# Kajtu_-DSP_analog_out.net
KiCad netlist of a schematic drawn in Altium Designer
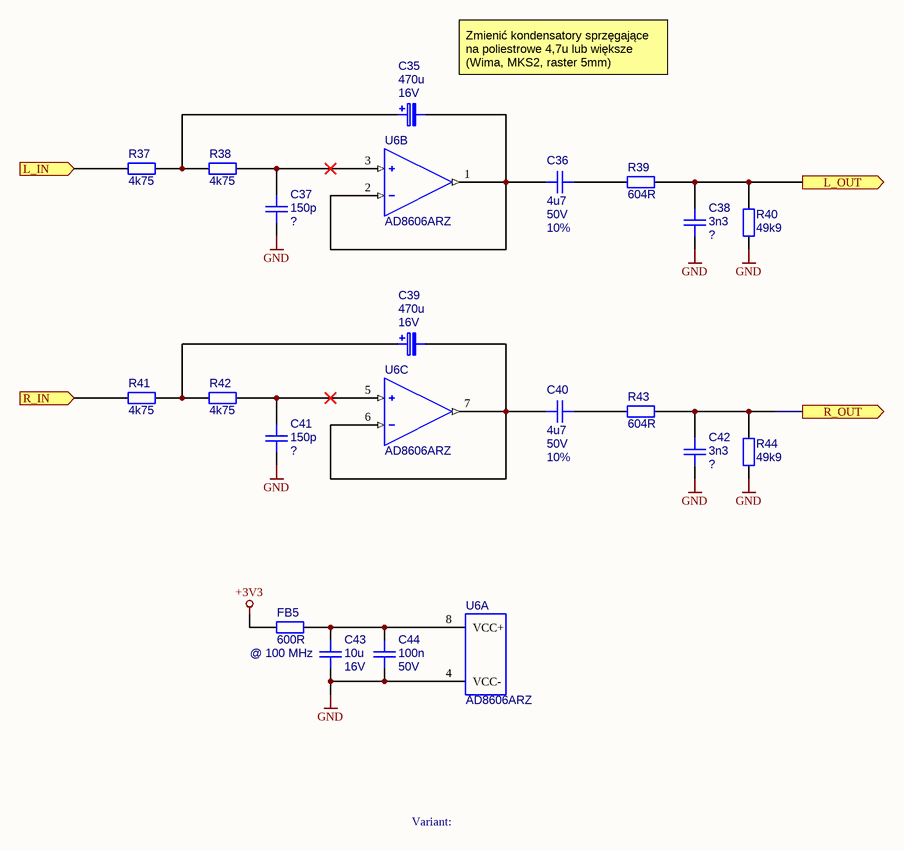
[diagram p0: Kajtuś-DSP_analog_out.SchDoc]

(export (version "E")
  (design (tool "Eeschema 10.0.6"))
  (components
    (comp (ref "C35")
      (value "470u")
      (footprint "CE_R3.5-D8-H11.5")
      (description "Kondensator elektrolityczny THD")
      (fields
        (field (name "PART NUMBER") "CE_R3.5-D8-H11.5_470u_16V")
        (field (name "MANUFACTURER") "Nichicon")
        (field (name "VOLTAGE") "16V")
      )
      (libsource (lib "AD_ostry_intlib") (part "CE_R3.5-D8-H11.5_470u_16V"))
    )
    (comp (ref "C36")
      (value "4u7")
      (footprint "C_R5-L7.2-W7.2-H13")
      (description "Kondensator tworzywowy")
      (fields
        (field (name "PART NUMBER") "C_R5-L7.2-W7.2-H13_4u7_50V_MKS2_10%")
        (field (name "MANUFACTURER") "Wima")
        (field (name "VOLTAGE") "50V")
        (field (name "TOLERANCE") "10%")
      )
      (libsource (lib "AD_ostry_intlib") (part "C_R5-L7.2-W7.2-H13_4u7_50V_MKS2_10%"))
    )
    (comp (ref "C37")
      (value "150p")
      (footprint "C_0603_MA")
      (description "Kondensator ceramiczny SMD")
      (fields (field (name "PART NUMBER") "C_SMD_MLCC_generic") (field (name "VOLTAGE") "?"))
      (libsource (lib "AD_ostry_intlib") (part "C_SMD_MLCC_generic"))
    )
    (comp (ref "C38")
      (value "3n3")
      (footprint "C_0603_MA")
      (description "Kondensator ceramiczny SMD")
      (fields (field (name "PART NUMBER") "C_SMD_MLCC_generic") (field (name "VOLTAGE") "?"))
      (libsource (lib "AD_ostry_intlib") (part "C_SMD_MLCC_generic"))
    )
    (comp (ref "C39")
      (value "470u")
      (footprint "CE_R3.5-D8-H11.5")
      (description "Kondensator elektrolityczny THD")
      (fields
        (field (name "PART NUMBER") "CE_R3.5-D8-H11.5_470u_16V")
        (field (name "MANUFACTURER") "Nichicon")
        (field (name "VOLTAGE") "16V")
      )
      (libsource (lib "AD_ostry_intlib") (part "CE_R3.5-D8-H11.5_470u_16V"))
    )
    (comp (ref "C40")
      (value "4u7")
      (footprint "C_R5-L7.2-W7.2-H13")
      (description "Kondensator tworzywowy")
      (fields
        (field (name "PART NUMBER") "C_R5-L7.2-W7.2-H13_4u7_50V_MKS2_10%")
        (field (name "MANUFACTURER") "Wima")
        (field (name "VOLTAGE") "50V")
        (field (name "TOLERANCE") "10%")
      )
      (libsource (lib "AD_ostry_intlib") (part "C_R5-L7.2-W7.2-H13_4u7_50V_MKS2_10%"))
    )
    (comp (ref "C41")
      (value "150p")
      (footprint "C_0603_MA")
      (description "Kondensator ceramiczny SMD")
      (fields (field (name "PART NUMBER") "C_SMD_MLCC_generic") (field (name "VOLTAGE") "?"))
      (libsource (lib "AD_ostry_intlib") (part "C_SMD_MLCC_generic"))
    )
    (comp (ref "C42")
      (value "3n3")
      (footprint "C_0603_MA")
      (description "Kondensator ceramiczny SMD")
      (fields (field (name "PART NUMBER") "C_SMD_MLCC_generic") (field (name "VOLTAGE") "?"))
      (libsource (lib "AD_ostry_intlib") (part "C_SMD_MLCC_generic"))
    )
    (comp (ref "C43")
      (value "10u")
      (footprint "C_0805_MA")
      (description "Kondensator ceramiczny SMD")
      (fields (field (name "PART NUMBER") "C_0805_10u_16V_X5R") (field (name "VOLTAGE") "16V"))
      (libsource (lib "AD_ostry_intlib") (part "C_0805_10u_16V_X5R"))
    )
    (comp (ref "C44")
      (value "100n")
      (footprint "C_0603_MA")
      (description "Kondensator ceramiczny SMD")
      (fields (field (name "PART NUMBER") "C_0603_100n_50V_X7R") (field (name "VOLTAGE") "50V"))
      (libsource (lib "AD_ostry_intlib") (part "C_0603_100n_50V_X7R"))
    )
    (comp (ref "FB5")
      (value "600R")
      (footprint "R_0603_MA")
      (description "Koralik ferrytowy")
      (fields
        (field (name "MANUFACTURER") "Yageo")
        (field (name "PART NUMBER") "FB_0603_PBY160808T-601Y_600R_1A")
        (field (name "@ FREQUENCY") "@ 100 MHz")
      )
      (libsource (lib "AD_ostry_intlib") (part "FB_0603_PBY160808T-601Y_600R_1A"))
    )
    (comp (ref "R37")
      (value "4k75")
      (footprint "R_1206_MA")
      (description "SMD resistor")
      (fields (field (name "PART NUMBER") "?"))
      (libsource (lib "AD_ostry_intlib") (part "R_SMD_generic"))
    )
    (comp (ref "R38")
      (value "4k75")
      (footprint "R_1206_MA")
      (description "SMD resistor")
      (fields (field (name "PART NUMBER") "?"))
      (libsource (lib "AD_ostry_intlib") (part "R_SMD_generic"))
    )
    (comp (ref "R39")
      (value "604R")
      (footprint "R_1206_MA")
      (description "SMD resistor")
      (fields (field (name "PART NUMBER") "?"))
      (libsource (lib "AD_ostry_intlib") (part "R_SMD_generic"))
    )
    (comp (ref "R40")
      (value "49k9")
      (footprint "R_1206_MA")
      (description "SMD resistor")
      (fields (field (name "PART NUMBER") "?"))
      (libsource (lib "AD_ostry_intlib") (part "R_SMD_generic"))
    )
    (comp (ref "R41")
      (value "4k75")
      (footprint "R_1206_MA")
      (description "SMD resistor")
      (fields (field (name "PART NUMBER") "?"))
      (libsource (lib "AD_ostry_intlib") (part "R_SMD_generic"))
    )
    (comp (ref "R42")
      (value "4k75")
      (footprint "R_1206_MA")
      (description "SMD resistor")
      (fields (field (name "PART NUMBER") "?"))
      (libsource (lib "AD_ostry_intlib") (part "R_SMD_generic"))
    )
    (comp (ref "R43")
      (value "604R")
      (footprint "R_1206_MA")
      (description "SMD resistor")
      (fields (field (name "PART NUMBER") "?"))
      (libsource (lib "AD_ostry_intlib") (part "R_SMD_generic"))
    )
    (comp (ref "R44")
      (value "49k9")
      (footprint "R_1206_MA")
      (description "SMD resistor")
      (fields (field (name "PART NUMBER") "?"))
      (libsource (lib "AD_ostry_intlib") (part "R_SMD_generic"))
    )
    (comp (ref "U6")
      (value "AD8606ARZ")
      (footprint "SO-8")
      (description "Precision, Low Noise, CMOS, Rail-to-Rail, Input/Output Operational Amplifier")
      (fields (field (name "MANUFACTURER") "Analog Devices"))
      (libsource (lib "") (part "U_AD8606ARZ_1"))
    )
  )
  (nets
    (net (code "1") (name "+3V3") (class "Default")
      (node (ref "FB5") (pin "1") (pinfunction "1_1") (pintype "passive"))
    )
    (net (code "2") (name "/L_IN") (class "Default")
      (node (ref "R37") (pin "2") (pinfunction "2_2") (pintype "passive"))
    )
    (net (code "3") (name "/L_OUT") (class "Default")
      (node (ref "C38") (pin "1") (pinfunction "1_1") (pintype "passive"))
      (node (ref "R39") (pin "1") (pinfunction "1_1") (pintype "passive"))
      (node (ref "R40") (pin "1") (pinfunction "1_1") (pintype "passive"))
    )
    (net (code "4") (name "/R_IN") (class "Default")
      (node (ref "R41") (pin "2") (pinfunction "2_2") (pintype "passive"))
    )
    (net (code "5") (name "/R_OUT") (class "Default")
      (node (ref "C42") (pin "1") (pinfunction "1_1") (pintype "passive"))
      (node (ref "R43") (pin "1") (pinfunction "1_1") (pintype "passive"))
      (node (ref "R44") (pin "1") (pinfunction "1_1") (pintype "passive"))
    )
    (net (code "6") (name "GND") (class "Default")
      (node (ref "C37") (pin "2") (pinfunction "2_2") (pintype "passive"))
      (node (ref "C38") (pin "2") (pinfunction "2_2") (pintype "passive"))
      (node (ref "C41") (pin "2") (pinfunction "2_2") (pintype "passive"))
      (node (ref "C42") (pin "2") (pinfunction "2_2") (pintype "passive"))
      (node (ref "C43") (pin "2") (pinfunction "2_2") (pintype "passive"))
      (node (ref "C44") (pin "2") (pinfunction "2_2") (pintype "passive"))
      (node (ref "R40") (pin "2") (pinfunction "2_2") (pintype "passive"))
      (node (ref "R44") (pin "2") (pinfunction "2_2") (pintype "passive"))
      (node (ref "U6") (pin "4") (pinfunction "VCC-_4") (pintype "power_in"))
    )
    (net (code "7") (name "Net-(C35-Pad1)") (class "Default")
      (node (ref "C35") (pin "1") (pinfunction "1_1") (pintype "passive"))
      (node (ref "R37") (pin "1") (pinfunction "1_1") (pintype "passive"))
      (node (ref "R38") (pin "2") (pinfunction "2_2") (pintype "passive"))
    )
    (net (code "8") (name "Net-(C36-Pad2)") (class "Default")
      (node (ref "C36") (pin "2") (pinfunction "2_2") (pintype "passive"))
      (node (ref "R39") (pin "2") (pinfunction "2_2") (pintype "passive"))
    )
    (net (code "9") (name "Net-(C39-Pad1)") (class "Default")
      (node (ref "C39") (pin "1") (pinfunction "1_1") (pintype "passive"))
      (node (ref "R41") (pin "1") (pinfunction "1_1") (pintype "passive"))
      (node (ref "R42") (pin "2") (pinfunction "2_2") (pintype "passive"))
    )
    (net (code "10") (name "Net-(C40-Pad2)") (class "Default")
      (node (ref "C40") (pin "2") (pinfunction "2_2") (pintype "passive"))
      (node (ref "R43") (pin "2") (pinfunction "2_2") (pintype "passive"))
    )
    (net (code "11") (name "Net-(U6A-VCC+)") (class "Default")
      (node (ref "C43") (pin "1") (pinfunction "1_1") (pintype "passive"))
      (node (ref "C44") (pin "1") (pinfunction "1_1") (pintype "passive"))
      (node (ref "FB5") (pin "2") (pinfunction "2_2") (pintype "passive"))
      (node (ref "U6") (pin "8") (pinfunction "VCC+_8") (pintype "power_in"))
    )
    (net (code "12") (name "Net-(U6B-+IN)") (class "Default")
      (node (ref "C37") (pin "1") (pinfunction "1_1") (pintype "passive"))
      (node (ref "R38") (pin "1") (pinfunction "1_1") (pintype "passive"))
      (node (ref "U6") (pin "3") (pinfunction "+IN_3") (pintype "input"))
    )
    (net (code "13") (name "Net-(U6B--IN)") (class "Default")
      (node (ref "C35") (pin "2") (pinfunction "2_2") (pintype "passive"))
      (node (ref "C36") (pin "1") (pinfunction "1_1") (pintype "passive"))
      (node (ref "U6") (pin "1") (pinfunction "Output_1") (pintype "output"))
      (node (ref "U6") (pin "2") (pinfunction "-IN_2") (pintype "input"))
    )
    (net (code "14") (name "Net-(U6C-+IN)") (class "Default")
      (node (ref "C41") (pin "1") (pinfunction "1_1") (pintype "passive"))
      (node (ref "R42") (pin "1") (pinfunction "1_1") (pintype "passive"))
      (node (ref "U6") (pin "5") (pinfunction "+IN_5") (pintype "input"))
    )
    (net (code "15") (name "Net-(U6C--IN)") (class "Default")
      (node (ref "C39") (pin "2") (pinfunction "2_2") (pintype "passive"))
      (node (ref "C40") (pin "1") (pinfunction "1_1") (pintype "passive"))
      (node (ref "U6") (pin "6") (pinfunction "-IN_6") (pintype "input"))
      (node (ref "U6") (pin "7") (pinfunction "Output_7") (pintype "output"))
    )
  )
)
